# LoRa.net
KiCad netlist of a schematic drawn in Altium Designer
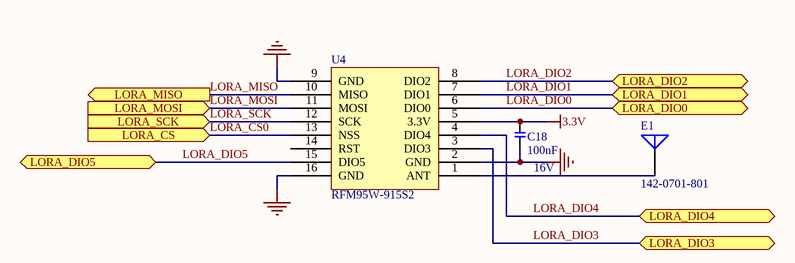
[diagram p0: LoRa.SchDoc]

(export (version "E")
  (design (tool "Eeschema 10.0.6"))
  (components
    (comp (ref "C18")
      (value "100nF")
      (footprint "T_CAPC0603X33N")
      (description "Capacitor Ceramic X7R 100nF 16V 10% 0603")
      (fields (field (name "TOLERANCE") "10%") (field (name "RATING") "16V"))
      (libsource (lib "Iris") (part "C-X7R-100nF-16V-10%-0603"))
    )
    (comp (ref "E1")
      (value "142-0701-801")
      (footprint "PIN1")
      (description "Generic Antenna")
      (fields (field (name "PUBLISHER") "Altium Limited"))
      (libsource (lib "Miscellaneous Devices") (part "Antenna"))
    )
    (comp (ref "U4")
      (value "RFM95W-915S2")
      (footprint "XCVR_RFM95W-915S2")
      (libsource (lib "Schlib1") (part "RFM95"))
    )
  )
  (nets
    (net (code "1") (name "/LORA_CS0") (class "Default")
      (node (ref "U4") (pin "13") (pinfunction "NSS_13") (pintype "passive"))
    )
    (net (code "2") (name "/LORA_DIO0") (class "Default")
      (node (ref "U4") (pin "6") (pinfunction "DIO0_6") (pintype "passive"))
    )
    (net (code "3") (name "/LORA_DIO1") (class "Default")
      (node (ref "U4") (pin "7") (pinfunction "DIO1_7") (pintype "passive"))
    )
    (net (code "4") (name "/LORA_DIO2") (class "Default")
      (node (ref "U4") (pin "8") (pinfunction "DIO2_8") (pintype "passive"))
    )
    (net (code "5") (name "/LORA_DIO3") (class "Default")
      (node (ref "U4") (pin "3") (pinfunction "DIO3_3") (pintype "passive"))
    )
    (net (code "6") (name "/LORA_DIO4") (class "Default")
      (node (ref "U4") (pin "4") (pinfunction "DIO4_4") (pintype "passive"))
    )
    (net (code "7") (name "/LORA_DIO5") (class "Default")
      (node (ref "U4") (pin "15") (pinfunction "DIO5_15") (pintype "passive"))
    )
    (net (code "8") (name "/LORA_MISO") (class "Default")
      (node (ref "U4") (pin "10") (pinfunction "MISO_10") (pintype "passive"))
    )
    (net (code "9") (name "/LORA_MOSI") (class "Default")
      (node (ref "U4") (pin "11") (pinfunction "MOSI_11") (pintype "passive"))
    )
    (net (code "10") (name "/LORA_SCK") (class "Default")
      (node (ref "U4") (pin "12") (pinfunction "SCK_12") (pintype "passive"))
    )
    (net (code "11") (name "3.3V") (class "Default")
      (node (ref "C18") (pin "2") (pinfunction "2_2") (pintype "passive"))
      (node (ref "U4") (pin "5") (pinfunction "3.3V_5") (pintype "passive"))
    )
    (net (code "12") (name "GND") (class "Default")
      (node (ref "C18") (pin "1") (pinfunction "1_1") (pintype "passive"))
      (node (ref "U4") (pin "16") (pinfunction "GND_16") (pintype "passive"))
      (node (ref "U4") (pin "2") (pinfunction "GND_2") (pintype "passive"))
      (node (ref "U4") (pin "9") (pinfunction "GND_9") (pintype "passive"))
    )
    (net (code "13") (name "Net-(E1-A)") (class "Default")
      (node (ref "E1") (pin "1") (pinfunction "A_1") (pintype "passive"))
      (node (ref "U4") (pin "1") (pinfunction "ANT_1") (pintype "passive"))
    )
    (net (code "14") (name "unconnected-(U4-RST-Pad14)") (class "Default")
      (node (ref "U4") (pin "14") (pinfunction "RST_14") (pintype "passive"))
    )
  )
)
